# NFC_Controller.net
KiCad netlist of a schematic drawn in Altium Designer
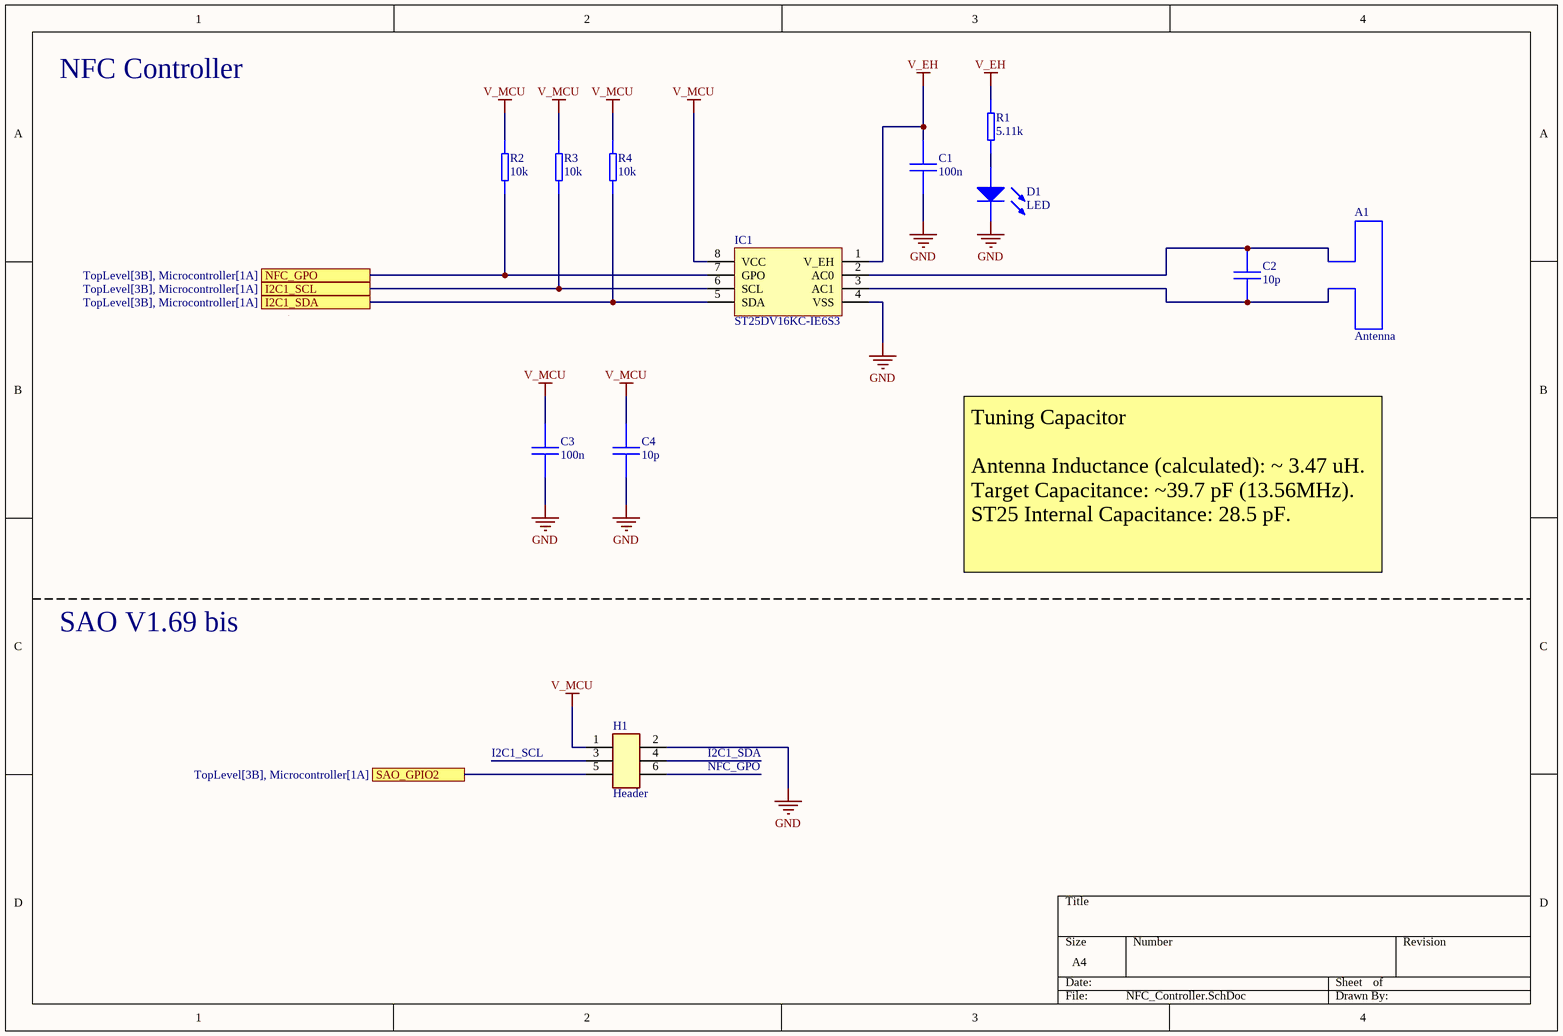
[diagram p0: NFC_Controller.SchDoc]

(export (version "E")
  (design (tool "Eeschema 10.0.6"))
  (components
    (comp (ref "A1")
      (value "Antenna")
      (footprint "NFC Antenna 45 x 37")
      (description "Antenna - Dual Ended")
      (libsource (lib "NFC_Luggage_Tag") (part "Antenna - Dual Ended 2"))
    )
    (comp (ref "C1")
      (value "100n")
      (footprint "CAP0805")
      (description "Non Polarized Capacitor")
      (libsource (lib "NFC_Luggage_Tag") (part "Capacitor - Non Polarized"))
    )
    (comp (ref "C2")
      (value "10p")
      (footprint "CAP0402")
      (description "Non Polarized Capacitor")
      (libsource (lib "NFC_Luggage_Tag") (part "Capacitor - Non Polarized_1"))
    )
    (comp (ref "C3")
      (value "100n")
      (footprint "CAP0805")
      (description "Non Polarized Capacitor")
      (libsource (lib "NFC_Luggage_Tag") (part "Capacitor - Non Polarized"))
    )
    (comp (ref "C4")
      (value "10p")
      (footprint "CAP0402")
      (description "Non Polarized Capacitor")
      (libsource (lib "NFC_Luggage_Tag") (part "Capacitor - Non Polarized_1"))
    )
    (comp (ref "D1")
      (value "LED")
      (footprint "LEDM2012X80N")
      (description "General Purpose LED")
      (libsource (lib "NFC_Luggage_Tag") (part "LED"))
    )
    (comp (ref "H1")
      (value "Header")
      (footprint "HEADER_2X3")
      (description "6-Pin 2 Row Header")
      (libsource (lib "NFC_Luggage_Tag") (part "6-Pin Header (3x2)"))
    )
    (comp (ref "IC1")
      (value "ST25DV16KC-IE6S3")
      (footprint "SOIC8")
      (description "Integrated Circuit")
      (fields (field (name "MOUSER PART NUMBER") "511-ST25DV16KC-IE6S3"))
      (libsource (lib "NFC_Luggage_Tag") (part "ST25DV16KC-IE6S3"))
    )
    (comp (ref "R1")
      (value "5.11k")
      (footprint "RESC0805")
      (description "Resistor")
      (libsource (lib "NFC_Luggage_Tag") (part "Resistor_1"))
    )
    (comp (ref "R2")
      (value "10k")
      (footprint "RESC0805")
      (description "Resistor")
      (libsource (lib "NFC_Luggage_Tag") (part "Resistor_2"))
    )
    (comp (ref "R3")
      (value "10k")
      (footprint "RESC0805")
      (description "Resistor")
      (libsource (lib "NFC_Luggage_Tag") (part "Resistor_2"))
    )
    (comp (ref "R4")
      (value "10k")
      (footprint "RESC0805")
      (description "Resistor")
      (libsource (lib "NFC_Luggage_Tag") (part "Resistor_2"))
    )
  )
  (nets
    (net (code "1") (name "/I2C1_SCL") (class "Default")
      (node (ref "IC1") (pin "6") (pinfunction "SCL_6") (pintype "passive"))
      (node (ref "R3") (pin "2") (pintype "passive"))
    )
    (net (code "2") (name "/I2C1_SDA") (class "Default")
      (node (ref "IC1") (pin "5") (pinfunction "SDA_5") (pintype "passive"))
      (node (ref "R4") (pin "2") (pintype "passive"))
    )
    (net (code "3") (name "/NFC_GPO") (class "Default")
      (node (ref "IC1") (pin "7") (pinfunction "GPO_7") (pintype "passive"))
      (node (ref "R2") (pin "2") (pintype "passive"))
    )
    (net (code "4") (name "/SAO_GPIO2") (class "Default") (node (ref "H1") (pin "5") (pintype "passive")))
    (net (code "5") (name "GND") (class "Default")
      (node (ref "C1") (pin "2") (pintype "passive"))
      (node (ref "C3") (pin "2") (pintype "passive"))
      (node (ref "C4") (pin "2") (pintype "passive"))
      (node (ref "D1") (pin "1") (pinfunction "K_1") (pintype "passive"))
      (node (ref "H1") (pin "2") (pintype "passive"))
      (node (ref "IC1") (pin "4") (pinfunction "VSS_4") (pintype "passive"))
    )
    (net (code "6") (name "Net-(D1-A)") (class "Default")
      (node (ref "D1") (pin "2") (pinfunction "A_2") (pintype "passive"))
      (node (ref "R1") (pin "2") (pintype "passive"))
    )
    (net (code "7") (name "Net-(IC1-AC0)") (class "Default")
      (node (ref "A1") (pin "1") (pintype "passive"))
      (node (ref "C2") (pin "1") (pintype "passive"))
      (node (ref "IC1") (pin "2") (pinfunction "AC0_2") (pintype "passive"))
    )
    (net (code "8") (name "Net-(IC1-AC1)") (class "Default")
      (node (ref "A1") (pin "2") (pintype "passive"))
      (node (ref "C2") (pin "2") (pintype "passive"))
      (node (ref "IC1") (pin "3") (pinfunction "AC1_3") (pintype "passive"))
    )
    (net (code "9") (name "V_EH") (class "Default")
      (node (ref "C1") (pin "1") (pintype "passive"))
      (node (ref "IC1") (pin "1") (pinfunction "V_EH_1") (pintype "passive"))
      (node (ref "R1") (pin "1") (pintype "passive"))
    )
    (net (code "10") (name "V_MCU") (class "Default")
      (node (ref "C3") (pin "1") (pintype "passive"))
      (node (ref "C4") (pin "1") (pintype "passive"))
      (node (ref "H1") (pin "1") (pintype "passive"))
      (node (ref "IC1") (pin "8") (pinfunction "VCC_8") (pintype "passive"))
      (node (ref "R2") (pin "1") (pintype "passive"))
      (node (ref "R3") (pin "1") (pintype "passive"))
      (node (ref "R4") (pin "1") (pintype "passive"))
    )
    (net (code "11") (name "unconnected-(H1-Pad3)") (class "Default")
      (node (ref "H1") (pin "3") (pintype "passive"))
    )
    (net (code "12") (name "unconnected-(H1-Pad4)") (class "Default")
      (node (ref "H1") (pin "4") (pintype "passive"))
    )
    (net (code "13") (name "unconnected-(H1-Pad6)") (class "Default")
      (node (ref "H1") (pin "6") (pintype "passive"))
    )
  )
)
